# EEM_Connectors.net
KiCad netlist of a schematic drawn in Altium Designer
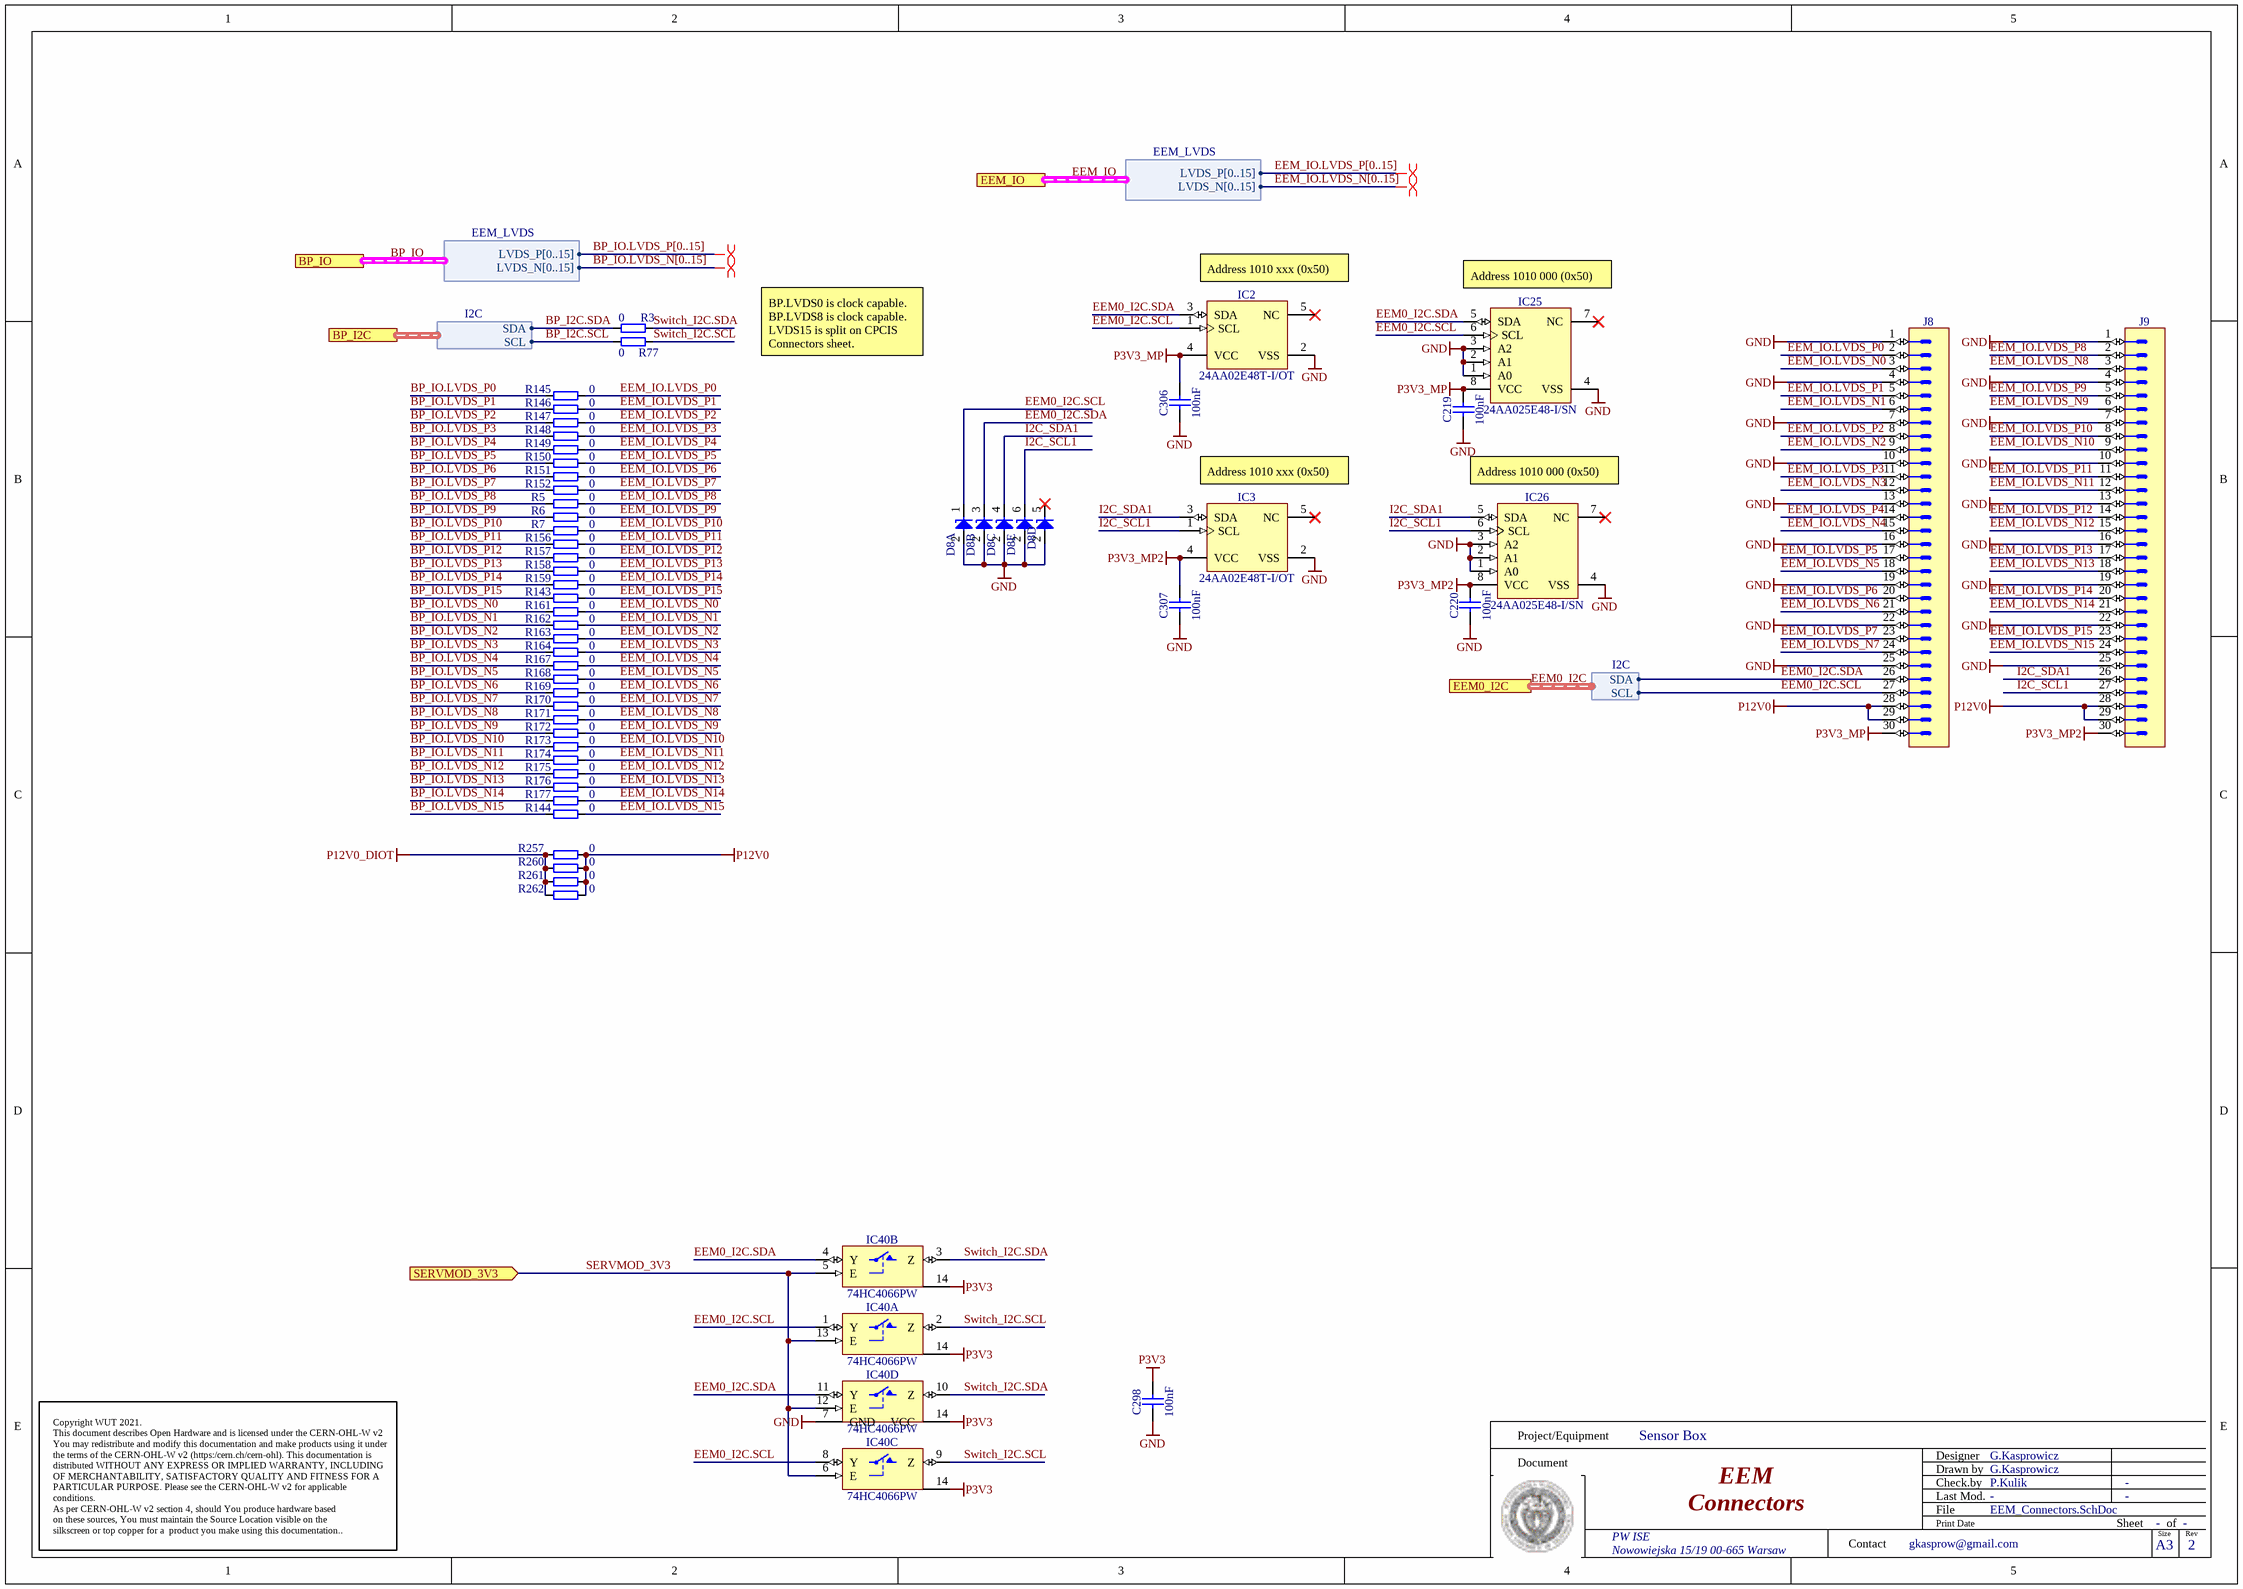
[diagram p0: EEM_Connectors.SchDoc]

(export (version "E")
  (design (tool "Eeschema 10.0.6"))
  (components
    (comp (ref "C219")
      (value "100nF")
      (footprint "CAPC1005X55N")
      (description "Non-polarised capacitor")
      (fields
        (field (name "PART NUMBER") "CC0402_100NF_50V_10%_X7R")
        (field (name "VOLTAGE") "50V")
        (field (name "AUTHOR") "CERN DEM MR")
      )
      (libsource (lib "Capacitors") (part "Capacitor - non polarized"))
    )
    (comp (ref "C220")
      (value "100nF")
      (footprint "CAPC1005X55N")
      (description "Non-polarised capacitor")
      (fields
        (field (name "PART NUMBER") "CC0402_100NF_50V_10%_X7R")
        (field (name "VOLTAGE") "50V")
        (field (name "AUTHOR") "CERN DEM MR")
      )
      (libsource (lib "Capacitors") (part "Capacitor - non polarized"))
    )
    (comp (ref "C298")
      (value "100nF")
      (footprint "CAPC1005X55N")
      (description "Non-polarised capacitor")
      (fields
        (field (name "PART NUMBER") "CC0402_100NF_50V_10%_X7R")
        (field (name "VOLTAGE") "50V")
        (field (name "AUTHOR") "CERN DEM MR")
      )
      (libsource (lib "Capacitors") (part "Capacitor - non polarized"))
    )
    (comp (ref "C306")
      (value "100nF")
      (footprint "CAPC1005X55N")
      (description "Non-polarised capacitor")
      (fields
        (field (name "PART NUMBER") "CC0402_100NF_50V_10%_X7R")
        (field (name "VOLTAGE") "50V")
        (field (name "AUTHOR") "CERN DEM MR")
      )
      (libsource (lib "Capacitors") (part "Capacitor - non polarized"))
    )
    (comp (ref "C307")
      (value "100nF")
      (footprint "CAPC1005X55N")
      (description "Non-polarised capacitor")
      (fields
        (field (name "PART NUMBER") "CC0402_100NF_50V_10%_X7R")
        (field (name "VOLTAGE") "50V")
        (field (name "AUTHOR") "CERN DEM MR")
      )
      (libsource (lib "Capacitors") (part "Capacitor - non polarized"))
    )
    (comp (ref "D8")
      (value "PESD3V3L5UY")
      (footprint "SOT65P210X110-6N")
      (description "Fivefold ESD Protection Diode Arrays")
      (fields
        (field (name "VOLTAGE") "3.3V")
        (field (name "POWER") "200W")
        (field (name "AUTHOR") "CERN DEM WB")
      )
      (libsource (lib "ICs And Semiconductors") (part "PESD Array 5diodes 6pins Common anode2"))
    )
    (comp (ref "IC2")
      (value "24AA02E48T-I/OT")
      (footprint "SOT95P280X145-5N")
      (description "1.7V-5.5V, 2K I2C Serial EEPROM With EUI-48 Node Identity")
      (fields (field (name "MANUFACTURER") "MICROCHIP TECHNOLOGY") (field (name "AUTHOR") "CERN DEM MR"))
      (libsource (lib "ICs And Semiconductors") (part "24AA02E48T-I/OT"))
    )
    (comp (ref "IC3")
      (value "24AA02E48T-I/OT")
      (footprint "SOT95P280X145-5N")
      (description "1.7V-5.5V, 2K I2C Serial EEPROM With EUI-48 Node Identity")
      (fields (field (name "MANUFACTURER") "MICROCHIP TECHNOLOGY") (field (name "AUTHOR") "CERN DEM MR"))
      (libsource (lib "ICs And Semiconductors") (part "24AA02E48T-I/OT"))
    )
    (comp (ref "IC25")
      (value "24AA025E48-I/SN")
      (footprint "SOIC127P600X175-8N")
      (description "1.7V-5.5V, 2K I2C™ Serial EEPROMs with EUI-48™ Node Identity")
      (fields (field (name "MANUFACTURER") "MICROCHIP TECHNOLOGY") (field (name "AUTHOR") "CERN DEM MR"))
      (libsource (lib "ICs And Semiconductors") (part "24AA025E48-I/SN"))
    )
    (comp (ref "IC26")
      (value "24AA025E48-I/SN")
      (footprint "SOIC127P600X175-8N")
      (description "1.7V-5.5V, 2K I2C™ Serial EEPROMs with EUI-48™ Node Identity")
      (fields (field (name "MANUFACTURER") "MICROCHIP TECHNOLOGY") (field (name "AUTHOR") "CERN DEM MR"))
      (libsource (lib "ICs And Semiconductors") (part "24AA025E48-I/SN"))
    )
    (comp (ref "IC40")
      (value "74HC4066PW")
      (footprint "SOP65P640X110-14N")
      (fields (field (name "MANUFACTURER") "NXP SEMICONDUCTORS") (field (name "AUTHOR") "CERN DEM JLC"))
      (libsource (lib "ICs And Semiconductors") (part "4066"))
    )
    (comp (ref "J8")
      (value "~")
      (footprint "3M_N2530-6002RB")
      (description "Connector 30 Male")
      (fields
        (field (name "PART NUMBER") "3M_N2530-6002RB")
        (field (name "MANUFACTURER") "3M")
        (field (name "AUTHOR") "CERN DEM JLC")
      )
      (libsource (lib "Connectors") (part "Connector 30 Male"))
    )
    (comp (ref "J9")
      (value "~")
      (footprint "3M_N2530-6002RB")
      (description "Connector 30 Male")
      (fields
        (field (name "PART NUMBER") "3M_N2530-6002RB")
        (field (name "MANUFACTURER") "3M")
        (field (name "AUTHOR") "CERN DEM JLC")
      )
      (libsource (lib "Connectors") (part "Connector 30 Male"))
    )
    (comp (ref "R3")
      (value "0")
      (footprint "RESC1005X40N")
      (description "Resistor")
      (fields
        (field (name "PART NUMBER") "R0402_0R_JUMPER")
        (field (name "MANUFACTURER") "GENERIC")
        (field (name "AUTHOR") "CERN DEM JLC")
      )
      (libsource (lib "Resistors") (part "Resistor"))
    )
    (comp (ref "R5")
      (value "0")
      (footprint "RESC1005X40N")
      (description "Resistor")
      (fields
        (field (name "PART NUMBER") "R0402_0R_JUMPER")
        (field (name "MANUFACTURER") "GENERIC")
        (field (name "AUTHOR") "CERN DEM JLC")
      )
      (libsource (lib "Resistors") (part "Resistor"))
    )
    (comp (ref "R6")
      (value "0")
      (footprint "RESC1005X40N")
      (description "Resistor")
      (fields
        (field (name "PART NUMBER") "R0402_0R_JUMPER")
        (field (name "MANUFACTURER") "GENERIC")
        (field (name "AUTHOR") "CERN DEM JLC")
      )
      (libsource (lib "Resistors") (part "Resistor"))
    )
    (comp (ref "R7")
      (value "0")
      (footprint "RESC1005X40N")
      (description "Resistor")
      (fields
        (field (name "PART NUMBER") "R0402_0R_JUMPER")
        (field (name "MANUFACTURER") "GENERIC")
        (field (name "AUTHOR") "CERN DEM JLC")
      )
      (libsource (lib "Resistors") (part "Resistor"))
    )
    (comp (ref "R77")
      (value "0")
      (footprint "RESC1005X40N")
      (description "Resistor")
      (fields
        (field (name "PART NUMBER") "R0402_0R_JUMPER")
        (field (name "MANUFACTURER") "GENERIC")
        (field (name "AUTHOR") "CERN DEM JLC")
      )
      (libsource (lib "Resistors") (part "Resistor"))
    )
    (comp (ref "R143")
      (value "0")
      (footprint "RESC1005X40N")
      (description "Resistor")
      (fields
        (field (name "PART NUMBER") "R0402_0R_JUMPER")
        (field (name "MANUFACTURER") "GENERIC")
        (field (name "AUTHOR") "CERN DEM JLC")
      )
      (libsource (lib "Resistors") (part "Resistor"))
    )
    (comp (ref "R144")
      (value "0")
      (footprint "RESC1005X40N")
      (description "Resistor")
      (fields
        (field (name "PART NUMBER") "R0402_0R_JUMPER")
        (field (name "MANUFACTURER") "GENERIC")
        (field (name "AUTHOR") "CERN DEM JLC")
      )
      (libsource (lib "Resistors") (part "Resistor"))
    )
    (comp (ref "R145")
      (value "0")
      (footprint "RESC1005X40N")
      (description "Resistor")
      (fields
        (field (name "PART NUMBER") "R0402_0R_JUMPER")
        (field (name "MANUFACTURER") "GENERIC")
        (field (name "AUTHOR") "CERN DEM JLC")
      )
      (libsource (lib "Resistors") (part "Resistor"))
    )
    (comp (ref "R146")
      (value "0")
      (footprint "RESC1005X40N")
      (description "Resistor")
      (fields
        (field (name "PART NUMBER") "R0402_0R_JUMPER")
        (field (name "MANUFACTURER") "GENERIC")
        (field (name "AUTHOR") "CERN DEM JLC")
      )
      (libsource (lib "Resistors") (part "Resistor"))
    )
    (comp (ref "R147")
      (value "0")
      (footprint "RESC1005X40N")
      (description "Resistor")
      (fields
        (field (name "PART NUMBER") "R0402_0R_JUMPER")
        (field (name "MANUFACTURER") "GENERIC")
        (field (name "AUTHOR") "CERN DEM JLC")
      )
      (libsource (lib "Resistors") (part "Resistor"))
    )
    (comp (ref "R148")
      (value "0")
      (footprint "RESC1005X40N")
      (description "Resistor")
      (fields
        (field (name "PART NUMBER") "R0402_0R_JUMPER")
        (field (name "MANUFACTURER") "GENERIC")
        (field (name "AUTHOR") "CERN DEM JLC")
      )
      (libsource (lib "Resistors") (part "Resistor"))
    )
    (comp (ref "R149")
      (value "0")
      (footprint "RESC1005X40N")
      (description "Resistor")
      (fields
        (field (name "PART NUMBER") "R0402_0R_JUMPER")
        (field (name "MANUFACTURER") "GENERIC")
        (field (name "AUTHOR") "CERN DEM JLC")
      )
      (libsource (lib "Resistors") (part "Resistor"))
    )
    (comp (ref "R150")
      (value "0")
      (footprint "RESC1005X40N")
      (description "Resistor")
      (fields
        (field (name "PART NUMBER") "R0402_0R_JUMPER")
        (field (name "MANUFACTURER") "GENERIC")
        (field (name "AUTHOR") "CERN DEM JLC")
      )
      (libsource (lib "Resistors") (part "Resistor"))
    )
    (comp (ref "R151")
      (value "0")
      (footprint "RESC1005X40N")
      (description "Resistor")
      (fields
        (field (name "PART NUMBER") "R0402_0R_JUMPER")
        (field (name "MANUFACTURER") "GENERIC")
        (field (name "AUTHOR") "CERN DEM JLC")
      )
      (libsource (lib "Resistors") (part "Resistor"))
    )
    (comp (ref "R152")
      (value "0")
      (footprint "RESC1005X40N")
      (description "Resistor")
      (fields
        (field (name "PART NUMBER") "R0402_0R_JUMPER")
        (field (name "MANUFACTURER") "GENERIC")
        (field (name "AUTHOR") "CERN DEM JLC")
      )
      (libsource (lib "Resistors") (part "Resistor"))
    )
    (comp (ref "R156")
      (value "0")
      (footprint "RESC1005X40N")
      (description "Resistor")
      (fields
        (field (name "PART NUMBER") "R0402_0R_JUMPER")
        (field (name "MANUFACTURER") "GENERIC")
        (field (name "AUTHOR") "CERN DEM JLC")
      )
      (libsource (lib "Resistors") (part "Resistor"))
    )
    (comp (ref "R157")
      (value "0")
      (footprint "RESC1005X40N")
      (description "Resistor")
      (fields
        (field (name "PART NUMBER") "R0402_0R_JUMPER")
        (field (name "MANUFACTURER") "GENERIC")
        (field (name "AUTHOR") "CERN DEM JLC")
      )
      (libsource (lib "Resistors") (part "Resistor"))
    )
    (comp (ref "R158")
      (value "0")
      (footprint "RESC1005X40N")
      (description "Resistor")
      (fields
        (field (name "PART NUMBER") "R0402_0R_JUMPER")
        (field (name "MANUFACTURER") "GENERIC")
        (field (name "AUTHOR") "CERN DEM JLC")
      )
      (libsource (lib "Resistors") (part "Resistor"))
    )
    (comp (ref "R159")
      (value "0")
      (footprint "RESC1005X40N")
      (description "Resistor")
      (fields
        (field (name "PART NUMBER") "R0402_0R_JUMPER")
        (field (name "MANUFACTURER") "GENERIC")
        (field (name "AUTHOR") "CERN DEM JLC")
      )
      (libsource (lib "Resistors") (part "Resistor"))
    )
    (comp (ref "R161")
      (value "0")
      (footprint "RESC1005X40N")
      (description "Resistor")
      (fields
        (field (name "PART NUMBER") "R0402_0R_JUMPER")
        (field (name "MANUFACTURER") "GENERIC")
        (field (name "AUTHOR") "CERN DEM JLC")
      )
      (libsource (lib "Resistors") (part "Resistor"))
    )
    (comp (ref "R162")
      (value "0")
      (footprint "RESC1005X40N")
      (description "Resistor")
      (fields
        (field (name "PART NUMBER") "R0402_0R_JUMPER")
        (field (name "MANUFACTURER") "GENERIC")
        (field (name "AUTHOR") "CERN DEM JLC")
      )
      (libsource (lib "Resistors") (part "Resistor"))
    )
    (comp (ref "R163")
      (value "0")
      (footprint "RESC1005X40N")
      (description "Resistor")
      (fields
        (field (name "PART NUMBER") "R0402_0R_JUMPER")
        (field (name "MANUFACTURER") "GENERIC")
        (field (name "AUTHOR") "CERN DEM JLC")
      )
      (libsource (lib "Resistors") (part "Resistor"))
    )
    (comp (ref "R164")
      (value "0")
      (footprint "RESC1005X40N")
      (description "Resistor")
      (fields
        (field (name "PART NUMBER") "R0402_0R_JUMPER")
        (field (name "MANUFACTURER") "GENERIC")
        (field (name "AUTHOR") "CERN DEM JLC")
      )
      (libsource (lib "Resistors") (part "Resistor"))
    )
    (comp (ref "R167")
      (value "0")
      (footprint "RESC1005X40N")
      (description "Resistor")
      (fields
        (field (name "PART NUMBER") "R0402_0R_JUMPER")
        (field (name "MANUFACTURER") "GENERIC")
        (field (name "AUTHOR") "CERN DEM JLC")
      )
      (libsource (lib "Resistors") (part "Resistor"))
    )
    (comp (ref "R168")
      (value "0")
      (footprint "RESC1005X40N")
      (description "Resistor")
      (fields
        (field (name "PART NUMBER") "R0402_0R_JUMPER")
        (field (name "MANUFACTURER") "GENERIC")
        (field (name "AUTHOR") "CERN DEM JLC")
      )
      (libsource (lib "Resistors") (part "Resistor"))
    )
    (comp (ref "R169")
      (value "0")
      (footprint "RESC1005X40N")
      (description "Resistor")
      (fields
        (field (name "PART NUMBER") "R0402_0R_JUMPER")
        (field (name "MANUFACTURER") "GENERIC")
        (field (name "AUTHOR") "CERN DEM JLC")
      )
      (libsource (lib "Resistors") (part "Resistor"))
    )
    (comp (ref "R170")
      (value "0")
      (footprint "RESC1005X40N")
      (description "Resistor")
      (fields
        (field (name "PART NUMBER") "R0402_0R_JUMPER")
        (field (name "MANUFACTURER") "GENERIC")
        (field (name "AUTHOR") "CERN DEM JLC")
      )
      (libsource (lib "Resistors") (part "Resistor"))
    )
    (comp (ref "R171")
      (value "0")
      (footprint "RESC1005X40N")
      (description "Resistor")
      (fields
        (field (name "PART NUMBER") "R0402_0R_JUMPER")
        (field (name "MANUFACTURER") "GENERIC")
        (field (name "AUTHOR") "CERN DEM JLC")
      )
      (libsource (lib "Resistors") (part "Resistor"))
    )
    (comp (ref "R172")
      (value "0")
      (footprint "RESC1005X40N")
      (description "Resistor")
      (fields
        (field (name "PART NUMBER") "R0402_0R_JUMPER")
        (field (name "MANUFACTURER") "GENERIC")
        (field (name "AUTHOR") "CERN DEM JLC")
      )
      (libsource (lib "Resistors") (part "Resistor"))
    )
    (comp (ref "R173")
      (value "0")
      (footprint "RESC1005X40N")
      (description "Resistor")
      (fields
        (field (name "PART NUMBER") "R0402_0R_JUMPER")
        (field (name "MANUFACTURER") "GENERIC")
        (field (name "AUTHOR") "CERN DEM JLC")
      )
      (libsource (lib "Resistors") (part "Resistor"))
    )
    (comp (ref "R174")
      (value "0")
      (footprint "RESC1005X40N")
      (description "Resistor")
      (fields
        (field (name "PART NUMBER") "R0402_0R_JUMPER")
        (field (name "MANUFACTURER") "GENERIC")
        (field (name "AUTHOR") "CERN DEM JLC")
      )
      (libsource (lib "Resistors") (part "Resistor"))
    )
    (comp (ref "R175")
      (value "0")
      (footprint "RESC1005X40N")
      (description "Resistor")
      (fields
        (field (name "PART NUMBER") "R0402_0R_JUMPER")
        (field (name "MANUFACTURER") "GENERIC")
        (field (name "AUTHOR") "CERN DEM JLC")
      )
      (libsource (lib "Resistors") (part "Resistor"))
    )
    (comp (ref "R176")
      (value "0")
      (footprint "RESC1005X40N")
      (description "Resistor")
      (fields
        (field (name "PART NUMBER") "R0402_0R_JUMPER")
        (field (name "MANUFACTURER") "GENERIC")
        (field (name "AUTHOR") "CERN DEM JLC")
      )
      (libsource (lib "Resistors") (part "Resistor"))
    )
    (comp (ref "R177")
      (value "0")
      (footprint "RESC1005X40N")
      (description "Resistor")
      (fields
        (field (name "PART NUMBER") "R0402_0R_JUMPER")
        (field (name "MANUFACTURER") "GENERIC")
        (field (name "AUTHOR") "CERN DEM JLC")
      )
      (libsource (lib "Resistors") (part "Resistor"))
    )
    (comp (ref "R257")
      (value "0")
      (footprint "RESC1005X40N")
      (description "Resistor")
      (fields
        (field (name "PART NUMBER") "R0402_0R_JUMPER")
        (field (name "MANUFACTURER") "GENERIC")
        (field (name "AUTHOR") "CERN DEM JLC")
      )
      (libsource (lib "Resistors") (part "Resistor"))
    )
    (comp (ref "R260")
      (value "0")
      (footprint "RESC1005X40N")
      (description "Resistor")
      (fields
        (field (name "PART NUMBER") "R0402_0R_JUMPER")
        (field (name "MANUFACTURER") "GENERIC")
        (field (name "AUTHOR") "CERN DEM JLC")
      )
      (libsource (lib "Resistors") (part "Resistor"))
    )
    (comp (ref "R261")
      (value "0")
      (footprint "RESC1005X40N")
      (description "Resistor")
      (fields
        (field (name "PART NUMBER") "R0402_0R_JUMPER")
        (field (name "MANUFACTURER") "GENERIC")
        (field (name "AUTHOR") "CERN DEM JLC")
      )
      (libsource (lib "Resistors") (part "Resistor"))
    )
    (comp (ref "R262")
      (value "0")
      (footprint "RESC1005X40N")
      (description "Resistor")
      (fields
        (field (name "PART NUMBER") "R0402_0R_JUMPER")
        (field (name "MANUFACTURER") "GENERIC")
        (field (name "AUTHOR") "CERN DEM JLC")
      )
      (libsource (lib "Resistors") (part "Resistor"))
    )
  )
  (nets
    (net (code "5") (name "/BP_I2C.SCL") (class "Default")
      (node (ref "R77") (pin "1") (pinfunction "1_1") (pintype "passive"))
    )
    (net (code "6") (name "/BP_I2C.SDA") (class "Default")
      (node (ref "R3") (pin "1") (pinfunction "1_1") (pintype "passive"))
    )
    (net (code "7") (name "/BP_IO.LVDS_N0") (class "Default")
      (node (ref "R161") (pin "1") (pinfunction "1_1") (pintype "passive"))
    )
    (net (code "8") (name "/BP_IO.LVDS_N1") (class "Default")
      (node (ref "R162") (pin "1") (pinfunction "1_1") (pintype "passive"))
    )
    (net (code "9") (name "/BP_IO.LVDS_N2") (class "Default")
      (node (ref "R163") (pin "1") (pinfunction "1_1") (pintype "passive"))
    )
    (net (code "10") (name "/BP_IO.LVDS_N3") (class "Default")
      (node (ref "R164") (pin "1") (pinfunction "1_1") (pintype "passive"))
    )
    (net (code "11") (name "/BP_IO.LVDS_N4") (class "Default")
      (node (ref "R167") (pin "1") (pinfunction "1_1") (pintype "passive"))
    )
    (net (code "12") (name "/BP_IO.LVDS_N5") (class "Default")
      (node (ref "R168") (pin "1") (pinfunction "1_1") (pintype "passive"))
    )
    (net (code "13") (name "/BP_IO.LVDS_N6") (class "Default")
      (node (ref "R169") (pin "1") (pinfunction "1_1") (pintype "passive"))
    )
    (net (code "14") (name "/BP_IO.LVDS_N7") (class "Default")
      (node (ref "R170") (pin "1") (pinfunction "1_1") (pintype "passive"))
    )
    (net (code "15") (name "/BP_IO.LVDS_N8") (class "Default")
      (node (ref "R171") (pin "1") (pinfunction "1_1") (pintype "passive"))
    )
    (net (code "16") (name "/BP_IO.LVDS_N9") (class "Default")
      (node (ref "R172") (pin "1") (pinfunction "1_1") (pintype "passive"))
    )
    (net (code "17") (name "/BP_IO.LVDS_N10") (class "Default")
      (node (ref "R173") (pin "1") (pinfunction "1_1") (pintype "passive"))
    )
    (net (code "18") (name "/BP_IO.LVDS_N11") (class "Default")
      (node (ref "R174") (pin "1") (pinfunction "1_1") (pintype "passive"))
    )
    (net (code "19") (name "/BP_IO.LVDS_N12") (class "Default")
      (node (ref "R175") (pin "1") (pinfunction "1_1") (pintype "passive"))
    )
    (net (code "20") (name "/BP_IO.LVDS_N13") (class "Default")
      (node (ref "R176") (pin "1") (pinfunction "1_1") (pintype "passive"))
    )
    (net (code "21") (name "/BP_IO.LVDS_N14") (class "Default")
      (node (ref "R177") (pin "1") (pinfunction "1_1") (pintype "passive"))
    )
    (net (code "22") (name "/BP_IO.LVDS_N15") (class "Default")
      (node (ref "R144") (pin "2") (pinfunction "2_2") (pintype "passive"))
    )
    (net (code "24") (name "/BP_IO.LVDS_P0") (class "Default")
      (node (ref "R145") (pin "1") (pinfunction "1_1") (pintype "passive"))
    )
    (net (code "25") (name "/BP_IO.LVDS_P1") (class "Default")
      (node (ref "R146") (pin "1") (pinfunction "1_1") (pintype "passive"))
    )
    (net (code "26") (name "/BP_IO.LVDS_P2") (class "Default")
      (node (ref "R147") (pin "1") (pinfunction "1_1") (pintype "passive"))
    )
    (net (code "27") (name "/BP_IO.LVDS_P3") (class "Default")
      (node (ref "R148") (pin "1") (pinfunction "1_1") (pintype "passive"))
    )
    (net (code "28") (name "/BP_IO.LVDS_P4") (class "Default")
      (node (ref "R149") (pin "1") (pinfunction "1_1") (pintype "passive"))
    )
    (net (code "29") (name "/BP_IO.LVDS_P5") (class "Default")
      (node (ref "R150") (pin "1") (pinfunction "1_1") (pintype "passive"))
    )
    (net (code "30") (name "/BP_IO.LVDS_P6") (class "Default")
      (node (ref "R151") (pin "1") (pinfunction "1_1") (pintype "passive"))
    )
    (net (code "31") (name "/BP_IO.LVDS_P7") (class "Default")
      (node (ref "R152") (pin "1") (pinfunction "1_1") (pintype "passive"))
    )
    (net (code "32") (name "/BP_IO.LVDS_P8") (class "Default")
      (node (ref "R5") (pin "1") (pinfunction "1_1") (pintype "passive"))
    )
    (net (code "33") (name "/BP_IO.LVDS_P9") (class "Default")
      (node (ref "R6") (pin "1") (pinfunction "1_1") (pintype "passive"))
    )
    (net (code "34") (name "/BP_IO.LVDS_P10") (class "Default")
      (node (ref "R7") (pin "1") (pinfunction "1_1") (pintype "passive"))
    )
    (net (code "35") (name "/BP_IO.LVDS_P11") (class "Default")
      (node (ref "R156") (pin "1") (pinfunction "1_1") (pintype "passive"))
    )
    (net (code "36") (name "/BP_IO.LVDS_P12") (class "Default")
      (node (ref "R157") (pin "1") (pinfunction "1_1") (pintype "passive"))
    )
    (net (code "37") (name "/BP_IO.LVDS_P13") (class "Default")
      (node (ref "R158") (pin "1") (pinfunction "1_1") (pintype "passive"))
    )
    (net (code "38") (name "/BP_IO.LVDS_P14") (class "Default")
      (node (ref "R159") (pin "1") (pinfunction "1_1") (pintype "passive"))
    )
    (net (code "39") (name "/BP_IO.LVDS_P15") (class "Default")
      (node (ref "R143") (pin "2") (pinfunction "2_2") (pintype "passive"))
    )
    (net (code "42") (name "/EEM0_I2C.SCL") (class "Default")
      (node (ref "D8") (pin "1") (pinfunction "C_1") (pintype "passive"))
      (node (ref "IC2") (pin "1") (pinfunction "SCL_1") (pintype "input"))
      (node (ref "IC25") (pin "6") (pinfunction "SCL_6") (pintype "input"))
      (node (ref "IC40") (pin "1") (pinfunction "Y_1") (pintype "bidirectional"))
      (node (ref "IC40") (pin "8") (pinfunction "Y_8") (pintype "bidirectional"))
      (node (ref "J8") (pin "27") (pinfunction "27_27") (pintype "bidirectional"))
    )
    (net (code "43") (name "/EEM0_I2C.SDA") (class "Default")
      (node (ref "D8") (pin "3") (pinfunction "C_3") (pintype "passive"))
      (node (ref "IC2") (pin "3") (pinfunction "SDA_3") (pintype "bidirectional"))
      (node (ref "IC25") (pin "5") (pinfunction "SDA_5") (pintype "bidirectional"))
      (node (ref "IC40") (pin "11") (pinfunction "Y_11") (pintype "bidirectional"))
      (node (ref "IC40") (pin "4") (pinfunction "Y_4") (pintype "bidirectional"))
      (node (ref "J8") (pin "26") (pinfunction "26_26") (pintype "bidirectional"))
    )
    (net (code "45") (name "/EEM_IO.LVDS_N0") (class "Default")
      (node (ref "J8") (pin "3") (pinfunction "3_3") (pintype "bidirectional"))
      (node (ref "R161") (pin "2") (pinfunction "2_2") (pintype "passive"))
    )
    (net (code "46") (name "/EEM_IO.LVDS_N1") (class "Default")
      (node (ref "J8") (pin "6") (pinfunction "6_6") (pintype "bidirectional"))
      (node (ref "R162") (pin "2") (pinfunction "2_2") (pintype "passive"))
    )
    (net (code "47") (name "/EEM_IO.LVDS_N2") (class "Default")
      (node (ref "J8") (pin "9") (pinfunction "9_9") (pintype "bidirectional"))
      (node (ref "R163") (pin "2") (pinfunction "2_2") (pintype "passive"))
    )
    (net (code "48") (name "/EEM_IO.LVDS_N3") (class "Default")
      (node (ref "J8") (pin "12") (pinfunction "12_12") (pintype "bidirectional"))
      (node (ref "R164") (pin "2") (pinfunction "2_2") (pintype "passive"))
    )
    (net (code "49") (name "/EEM_IO.LVDS_N4") (class "Default")
      (node (ref "J8") (pin "15") (pinfunction "15_15") (pintype "bidirectional"))
      (node (ref "R167") (pin "2") (pinfunction "2_2") (pintype "passive"))
    )
    (net (code "50") (name "/EEM_IO.LVDS_N5") (class "Default")
      (node (ref "J8") (pin "18") (pinfunction "18_18") (pintype "bidirectional"))
      (node (ref "R168") (pin "2") (pinfunction "2_2") (pintype "passive"))
    )
    (net (code "51") (name "/EEM_IO.LVDS_N6") (class "Default")
      (node (ref "J8") (pin "21") (pinfunction "21_21") (pintype "bidirectional"))
      (node (ref "R169") (pin "2") (pinfunction "2_2") (pintype "passive"))
    )
    (net (code "52") (name "/EEM_IO.LVDS_N7") (class "Default")
      (node (ref "J8") (pin "24") (pinfunction "24_24") (pintype "bidirectional"))
      (node (ref "R170") (pin "2") (pinfunction "2_2") (pintype "passive"))
    )
    (net (code "53") (name "/EEM_IO.LVDS_N8") (class "Default")
      (node (ref "J9") (pin "3") (pinfunction "3_3") (pintype "bidirectional"))
      (node (ref "R171") (pin "2") (pinfunction "2_2") (pintype "passive"))
    )
    (net (code "54") (name "/EEM_IO.LVDS_N9") (class "Default")
      (node (ref "J9") (pin "6") (pinfunction "6_6") (pintype "bidirectional"))
      (node (ref "R172") (pin "2") (pinfunction "2_2") (pintype "passive"))
    )
    (net (code "55") (name "/EEM_IO.LVDS_N10") (class "Default")
      (node (ref "J9") (pin "9") (pinfunction "9_9") (pintype "bidirectional"))
      (node (ref "R173") (pin "2") (pinfunction "2_2") (pintype "passive"))
    )
    (net (code "56") (name "/EEM_IO.LVDS_N11") (class "Default")
      (node (ref "J9") (pin "12") (pinfunction "12_12") (pintype "bidirectional"))
      (node (ref "R174") (pin "2") (pinfunction "2_2") (pintype "passive"))
    )
    (net (code "57") (name "/EEM_IO.LVDS_N12") (class "Default")
      (node (ref "J9") (pin "15") (pinfunction "15_15") (pintype "bidirectional"))
      (node (ref "R175") (pin "2") (pinfunction "2_2") (pintype "passive"))
    )
    (net (code "58") (name "/EEM_IO.LVDS_N13") (class "Default")
      (node (ref "J9") (pin "18") (pinfunction "18_18") (pintype "bidirectional"))
      (node (ref "R176") (pin "2") (pinfunction "2_2") (pintype "passive"))
    )
    (net (code "59") (name "/EEM_IO.LVDS_N14") (class "Default")
      (node (ref "J9") (pin "21") (pinfunction "21_21") (pintype "bidirectional"))
      (node (ref "R177") (pin "2") (pinfunction "2_2") (pintype "passive"))
    )
    (net (code "60") (name "/EEM_IO.LVDS_N15") (class "Default")
      (node (ref "J9") (pin "24") (pinfunction "24_24") (pintype "bidirectional"))
      (node (ref "R144") (pin "1") (pinfunction "1_1") (pintype "passive"))
    )
    (net (code "62") (name "/EEM_IO.LVDS_P0") (class "Default")
      (node (ref "J8") (pin "2") (pinfunction "2_2") (pintype "bidirectional"))
      (node (ref "R145") (pin "2") (pinfunction "2_2") (pintype "passive"))
    )
    (net (code "63") (name "/EEM_IO.LVDS_P1") (class "Default")
      (node (ref "J8") (pin "5") (pinfunction "5_5") (pintype "bidirectional"))
      (node (ref "R146") (pin "2") (pinfunction "2_2") (pintype "passive"))
    )
    (net (code "64") (name "/EEM_IO.LVDS_P2") (class "Default")
      (node (ref "J8") (pin "8") (pinfunction "8_8") (pintype "bidirectional"))
      (node (ref "R147") (pin "2") (pinfunction "2_2") (pintype "passive"))
    )
    (net (code "65") (name "/EEM_IO.LVDS_P3") (class "Default")
      (node (ref "J8") (pin "11") (pinfunction "11_11") (pintype "bidirectional"))
      (node (ref "R148") (pin "2") (pinfunction "2_2") (pintype "passive"))
    )
    (net (code "66") (name "/EEM_IO.LVDS_P4") (class "Default")
      (node (ref "J8") (pin "14") (pinfunction "14_14") (pintype "bidirectional"))
      (node (ref "R149") (pin "2") (pinfunction "2_2") (pintype "passive"))
    )
    (net (code "67") (name "/EEM_IO.LVDS_P5") (class "Default")
      (node (ref "J8") (pin "17") (pinfunction "17_17") (pintype "bidirectional"))
      (node (ref "R150") (pin "2") (pinfunction "2_2") (pintype "passive"))
    )
    (net (code "68") (name "/EEM_IO.LVDS_P6") (class "Default")
      (node (ref "J8") (pin "20") (pinfunction "20_20") (pintype "bidirectional"))
      (node (ref "R151") (pin "2") (pinfunction "2_2") (pintype "passive"))
    )
    (net (code "69") (name "/EEM_IO.LVDS_P7") (class "Default")
      (node (ref "J8") (pin "23") (pinfunction "23_23") (pintype "bidirectional"))
      (node (ref "R152") (pin "2") (pinfunction "2_2") (pintype "passive"))
    )
    (net (code "70") (name "/EEM_IO.LVDS_P8") (class "Default")
      (node (ref "J9") (pin "2") (pinfunction "2_2") (pintype "bidirectional"))
      (node (ref "R5") (pin "2") (pinfunction "2_2") (pintype "passive"))
    )
    (net (code "71") (name "/EEM_IO.LVDS_P9") (class "Default")
      (node (ref "J9") (pin "5") (pinfunction "5_5") (pintype "bidirectional"))
      (node (ref "R6") (pin "2") (pinfunction "2_2") (pintype "passive"))
    )
    (net (code "72") (name "/EEM_IO.LVDS_P10") (class "Default")
      (node (ref "J9") (pin "8") (pinfunction "8_8") (pintype "bidirectional"))
      (node (ref "R7") (pin "2") (pinfunction "2_2") (pintype "passive"))
    )
    (net (code "73") (name "/EEM_IO.LVDS_P11") (class "Default")
      (node (ref "J9") (pin "11") (pinfunction "11_11") (pintype "bidirectional"))
      (node (ref "R156") (pin "2") (pinfunction "2_2") (pintype "passive"))
    )
    (net (code "74") (name "/EEM_IO.LVDS_P12") (class "Default")
      (node (ref "J9") (pin "14") (pinfunction "14_14") (pintype "bidirectional"))
      (node (ref "R157") (pin "2") (pinfunction "2_2") (pintype "passive"))
    )
    (net (code "75") (name "/EEM_IO.LVDS_P13") (class "Default")
      (node (ref "J9") (pin "17") (pinfunction "17_17") (pintype "bidirectional"))
      (node (ref "R158") (pin "2") (pinfunction "2_2") (pintype "passive"))
    )
    (net (code "76") (name "/EEM_IO.LVDS_P14") (class "Default")
      (node (ref "J9") (pin "20") (pinfunction "20_20") (pintype "bidirectional"))
      (node (ref "R159") (pin "2") (pinfunction "2_2") (pintype "passive"))
    )
    (net (code "77") (name "/EEM_IO.LVDS_P15") (class "Default")
      (node (ref "J9") (pin "23") (pinfunction "23_23") (pintype "bidirectional"))
      (node (ref "R143") (pin "1") (pinfunction "1_1") (pintype "passive"))
    )
    (net (code "80") (name "/I2C_SCL1") (class "Default")
      (node (ref "D8") (pin "6") (pinfunction "C_6") (pintype "passive"))
      (node (ref "IC26") (pin "6") (pinfunction "SCL_6") (pintype "input"))
      (node (ref "IC3") (pin "1") (pinfunction "SCL_1") (pintype "input"))
      (node (ref "J9") (pin "27") (pinfunction "27_27") (pintype "bidirectional"))
    )
    (net (code "81") (name "/I2C_SDA1") (class "Default")
      (node (ref "D8") (pin "4") (pinfunction "C_4") (pintype "passive"))
      (node (ref "IC26") (pin "5") (pinfunction "SDA_5") (pintype "bidirectional"))
      (node (ref "IC3") (pin "3") (pinfunction "SDA_3") (pintype "bidirectional"))
      (node (ref "J9") (pin "26") (pinfunction "26_26") (pintype "bidirectional"))
    )
    (net (code "82") (name "/SERVMOD_3V3") (class "Default")
      (node (ref "IC40") (pin "12") (pinfunction "E_12") (pintype "input"))
      (node (ref "IC40") (pin "13") (pinfunction "E_13") (pintype "input"))
      (node (ref "IC40") (pin "5") (pinfunction "E_5") (pintype "input"))
      (node (ref "IC40") (pin "6") (pinfunction "E_6") (pintype "input"))
    )
    (net (code "83") (name "/Switch_I2C.SCL") (class "Default")
      (node (ref "IC40") (pin "2") (pinfunction "Z_2") (pintype "bidirectional"))
      (node (ref "IC40") (pin "9") (pinfunction "Z_9") (pintype "bidirectional"))
      (node (ref "R77") (pin "2") (pinfunction "2_2") (pintype "passive"))
    )
    (net (code "84") (name "/Switch_I2C.SDA") (class "Default")
      (node (ref "IC40") (pin "10") (pinfunction "Z_10") (pintype "bidirectional"))
      (node (ref "IC40") (pin "3") (pinfunction "Z_3") (pintype "bidirectional"))
      (node (ref "R3") (pin "2") (pinfunction "2_2") (pintype "passive"))
    )
    (net (code "86") (name "GND") (class "Default")
      (node (ref "C219") (pin "1") (pinfunction "1_1") (pintype "passive"))
      (node (ref "C220") (pin "1") (pinfunction "1_1") (pintype "passive"))
      (node (ref "C298") (pin "1") (pinfunction "1_1") (pintype "passive"))
      (node (ref "C306") (pin "1") (pinfunction "1_1") (pintype "passive"))
      (node (ref "C307") (pin "1") (pinfunction "1_1") (pintype "passive"))
      (node (ref "D8") (pin "2") (pinfunction "A_2") (pintype "passive"))
      (node (ref "IC2") (pin "2") (pinfunction "VSS_2") (pintype "power_in"))
      (node (ref "IC25") (pin "1") (pinfunction "A0_1") (pintype "input"))
      (node (ref "IC25") (pin "2") (pinfunction "A1_2") (pintype "input"))
      (node (ref "IC25") (pin "3") (pinfunction "A2_3") (pintype "input"))
      (node (ref "IC25") (pin "4") (pinfunction "VSS_4") (pintype "power_in"))
      (node (ref "IC26") (pin "1") (pinfunction "A0_1") (pintype "input"))
      (node (ref "IC26") (pin "2") (pinfunction "A1_2") (pintype "input"))
      (node (ref "IC26") (pin "3") (pinfunction "A2_3") (pintype "input"))
      (node (ref "IC26") (pin "4") (pinfunction "VSS_4") (pintype "power_in"))
      (node (ref "IC3") (pin "2") (pinfunction "VSS_2") (pintype "power_in"))
      (node (ref "IC40") (pin "7") (pinfunction "GND_7") (pintype "power_in"))
      (node (ref "J8") (pin "1") (pinfunction "1_1") (pintype "bidirectional"))
      (node (ref "J8") (pin "10") (pinfunction "10_10") (pintype "bidirectional"))
      (node (ref "J8") (pin "13") (pinfunction "13_13") (pintype "bidirectional"))
      (node (ref "J8") (pin "16") (pinfunction "16_16") (pintype "bidirectional"))
      (node (ref "J8") (pin "19") (pinfunction "19_19") (pintype "bidirectional"))
      (node (ref "J8") (pin "22") (pinfunction "22_22") (pintype "bidirectional"))
      (node (ref "J8") (pin "25") (pinfunction "25_25") (pintype "bidirectional"))
      (node (ref "J8") (pin "4") (pinfunction "4_4") (pintype "bidirectional"))
      (node (ref "J8") (pin "7") (pinfunction "7_7") (pintype "bidirectional"))
      (node (ref "J9") (pin "1") (pinfunction "1_1") (pintype "bidirectional"))
      (node (ref "J9") (pin "10") (pinfunction "10_10") (pintype "bidirectional"))
      (node (ref "J9") (pin "13") (pinfunction "13_13") (pintype "bidirectional"))
      (node (ref "J9") (pin "16") (pinfunction "16_16") (pintype "bidirectional"))
      (node (ref "J9") (pin "19") (pinfunction "19_19") (pintype "bidirectional"))
      (node (ref "J9") (pin "22") (pinfunction "22_22") (pintype "bidirectional"))
      (node (ref "J9") (pin "25") (pinfunction "25_25") (pintype "bidirectional"))
      (node (ref "J9") (pin "4") (pinfunction "4_4") (pintype "bidirectional"))
      (node (ref "J9") (pin "7") (pinfunction "7_7") (pintype "bidirectional"))
    )
    (net (code "87") (name "P3V3") (class "Default")
      (node (ref "C298") (pin "2") (pinfunction "2_2") (pintype "passive"))
      (node (ref "IC40") (pin "14") (pinfunction "VCC_14") (pintype "power_in"))
    )
    (net (code "88") (name "P3V3_MP") (class "Default")
      (node (ref "C219") (pin "2") (pinfunction "2_2") (pintype "passive"))
      (node (ref "C306") (pin "2") (pinfunction "2_2") (pintype "passive"))
      (node (ref "IC2") (pin "4") (pinfunction "VCC_4") (pintype "power_in"))
      (node (ref "IC25") (pin "8") (pinfunction "VCC_8") (pintype "power_in"))
      (node (ref "J8") (pin "30") (pinfunction "30_30") (pintype "bidirectional"))
    )
    (net (code "89") (name "P3V3_MP2") (class "Default")
      (node (ref "C220") (pin "2") (pinfunction "2_2") (pintype "passive"))
      (node (ref "C307") (pin "2") (pinfunction "2_2") (pintype "passive"))
      (node (ref "IC26") (pin "8") (pinfunction "VCC_8") (pintype "power_in"))
      (node (ref "IC3") (pin "4") (pinfunction "VCC_4") (pintype "power_in"))
      (node (ref "J9") (pin "30") (pinfunction "30_30") (pintype "bidirectional"))
    )
    (net (code "90") (name "P12V0") (class "Default")
      (node (ref "J8") (pin "28") (pinfunction "28_28") (pintype "bidirectional"))
      (node (ref "J8") (pin "29") (pinfunction "29_29") (pintype "bidirectional"))
      (node (ref "J9") (pin "28") (pinfunction "28_28") (pintype "bidirectional"))
      (node (ref "J9") (pin "29") (pinfunction "29_29") (pintype "bidirectional"))
      (node (ref "R257") (pin "2") (pinfunction "2_2") (pintype "passive"))
      (node (ref "R260") (pin "2") (pinfunction "2_2") (pintype "passive"))
      (node (ref "R261") (pin "2") (pinfunction "2_2") (pintype "passive"))
      (node (ref "R262") (pin "2") (pinfunction "2_2") (pintype "passive"))
    )
    (net (code "91") (name "P12V0_DIOT") (class "Default")
      (node (ref "R257") (pin "1") (pinfunction "1_1") (pintype "passive"))
      (node (ref "R260") (pin "1") (pinfunction "1_1") (pintype "passive"))
      (node (ref "R261") (pin "1") (pinfunction "1_1") (pintype "passive"))
      (node (ref "R262") (pin "1") (pinfunction "1_1") (pintype "passive"))
    )
    (net (code "92") (name "unconnected-(D8D-C-Pad5)") (class "Default")
      (node (ref "D8") (pin "5") (pinfunction "C_5") (pintype "passive+no_connect"))
    )
    (net (code "93") (name "unconnected-(IC2-NC-Pad5)") (class "Default")
      (node (ref "IC2") (pin "5") (pinfunction "NC_5") (pintype "passive+no_connect"))
    )
    (net (code "94") (name "unconnected-(IC3-NC-Pad5)") (class "Default")
      (node (ref "IC3") (pin "5") (pinfunction "NC_5") (pintype "passive+no_connect"))
    )
    (net (code "95") (name "unconnected-(IC25-NC-Pad7)") (class "Default")
      (node (ref "IC25") (pin "7") (pinfunction "NC_7") (pintype "passive+no_connect"))
    )
    (net (code "96") (name "unconnected-(IC26-NC-Pad7)") (class "Default")
      (node (ref "IC26") (pin "7") (pinfunction "NC_7") (pintype "passive+no_connect"))
    )
  )
)
